# house-sensor4pre.net
KiCad netlist of a schematic drawn in EAGLE
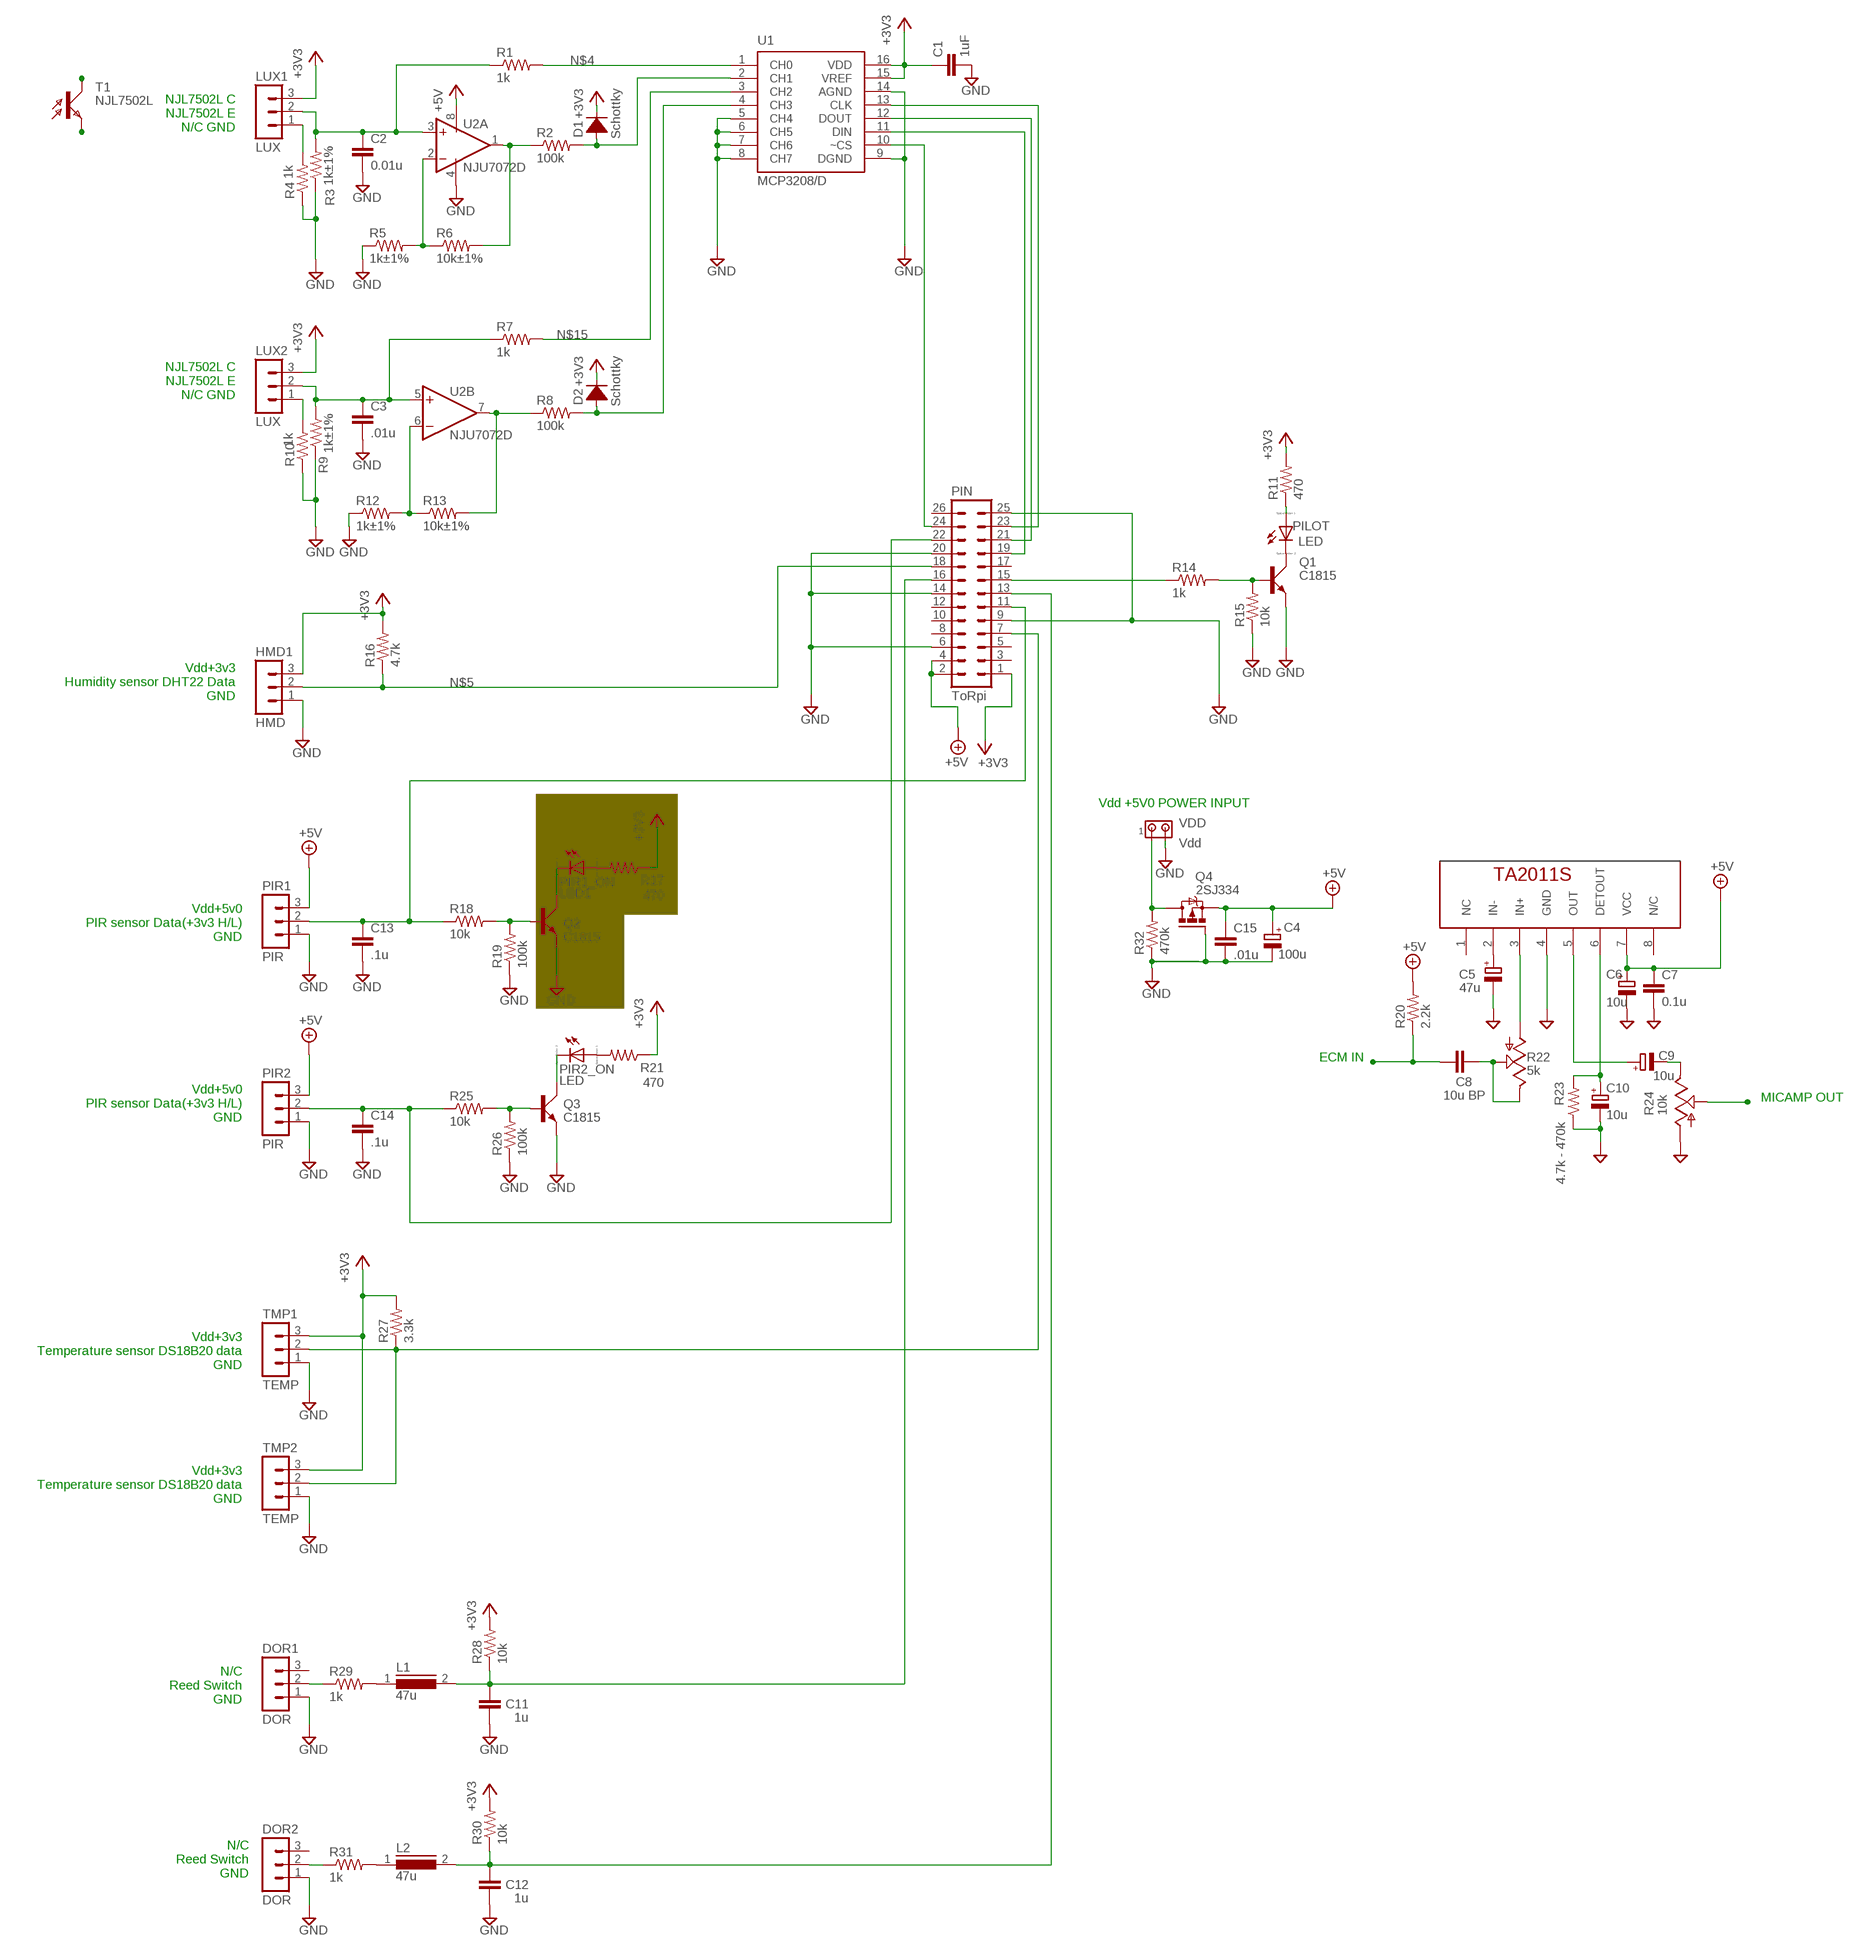
[diagram p0: schematic, sheet 1]

(export (version "E")
  (design (tool "Eeschema 10.0.6"))
  (components
    (comp (ref "C1")
      (value "1uF")
      (footprint "eagle-import:C025-025X050")
      (libsource (lib "eagle-import") (part "C-EU025-025X050"))
    )
    (comp (ref "C2")
      (value "0.01u")
      (footprint "eagle-import:C025-024X044")
      (libsource (lib "eagle-import") (part "C-EU025-024X044"))
    )
    (comp (ref "C3")
      (value ".01u")
      (footprint "eagle-import:C025-024X044")
      (libsource (lib "eagle-import") (part "C-EU025-024X044"))
    )
    (comp (ref "C4")
      (value "100u")
      (footprint "eagle-import:E1,8-4")
      (libsource (lib "eagle-import") (part "resistor_CPOL-EUE1.8-4"))
    )
    (comp (ref "C5")
      (value "47u")
      (footprint "eagle-import:E1,8-4")
      (libsource (lib "eagle-import") (part "rcl_CPOL-EUE1.8-4"))
    )
    (comp (ref "C6")
      (value "10u")
      (footprint "eagle-import:E1,8-4")
      (libsource (lib "eagle-import") (part "rcl_CPOL-EUE1.8-4"))
    )
    (comp (ref "C7")
      (value "0.1u")
      (footprint "eagle-import:C025-024X044")
      (libsource (lib "eagle-import") (part "C"))
    )
    (comp (ref "C8")
      (value "10u BP")
      (footprint "eagle-import:C025-024X044")
      (libsource (lib "eagle-import") (part "C"))
    )
    (comp (ref "C9")
      (value "10u")
      (footprint "eagle-import:E1,8-4")
      (libsource (lib "eagle-import") (part "rcl_CPOL-EUE1.8-4"))
    )
    (comp (ref "C10")
      (value "10u")
      (footprint "eagle-import:E1,8-4")
      (libsource (lib "eagle-import") (part "CPOL-EUE1.8-4"))
    )
    (comp (ref "C11")
      (value "1u")
      (footprint "eagle-import:C050-024X044")
      (libsource (lib "eagle-import") (part "C-EU050-024X044"))
    )
    (comp (ref "C12")
      (value "1u")
      (footprint "eagle-import:C050-024X044")
      (libsource (lib "eagle-import") (part "C-EU050-024X044"))
    )
    (comp (ref "C13")
      (value ".1u")
      (footprint "eagle-import:C025-030X050")
      (libsource (lib "eagle-import") (part "C-EU025-030X050"))
    )
    (comp (ref "C14")
      (value ".1u")
      (footprint "eagle-import:C025-030X050")
      (libsource (lib "eagle-import") (part "C-EU025-030X050"))
    )
    (comp (ref "C15")
      (value ".01u")
      (footprint "eagle-import:C025-025X050")
      (libsource (lib "eagle-import") (part "C-EU025-025X050"))
    )
    (comp (ref "D1")
      (value "Schottky")
      (footprint "eagle-import:DIODE_V")
      (libsource (lib "eagle-import") (part "DIODE_V"))
    )
    (comp (ref "D2")
      (value "Schottky")
      (footprint "eagle-import:DIODE_V")
      (libsource (lib "eagle-import") (part "DIODE_V"))
    )
    (comp (ref "DOR1")
      (value "DOR")
      (footprint "eagle-import:MA03-1")
      (libsource (lib "eagle-import") (part "MA03-1"))
    )
    (comp (ref "DOR2")
      (value "DOR")
      (footprint "eagle-import:MA03-1")
      (libsource (lib "eagle-import") (part "MA03-1"))
    )
    (comp (ref "HMD1")
      (value "HMD")
      (footprint "eagle-import:MA03-1")
      (libsource (lib "eagle-import") (part "MA03-1"))
    )
    (comp (ref "L1")
      (value "47u")
      (footprint "eagle-import:LBC-SE")
      (libsource (lib "eagle-import") (part "LBC-SE"))
    )
    (comp (ref "L2")
      (value "47u")
      (footprint "eagle-import:LBC-SE")
      (libsource (lib "eagle-import") (part "LBC-SE"))
    )
    (comp (ref "LUX1")
      (value "LUX")
      (footprint "eagle-import:MA03-1")
      (libsource (lib "eagle-import") (part "MA03-1"))
    )
    (comp (ref "LUX2")
      (value "LUX")
      (footprint "eagle-import:MA03-1")
      (libsource (lib "eagle-import") (part "MA03-1"))
    )
    (comp (ref "PILOT")
      (value "LED")
      (footprint "eagle-import:LED_LD260")
      (libsource (lib "eagle-import") (part "LED_ELD260"))
    )
    (comp (ref "PIN")
      (value "ToRpi")
      (footprint "eagle-import:MA13-2")
      (libsource (lib "eagle-import") (part "MA13-2"))
    )
    (comp (ref "PIR1")
      (value "PIR")
      (footprint "eagle-import:MA03-1")
      (libsource (lib "eagle-import") (part "MA03-1"))
    )
    (comp (ref "PIR1_ON")
      (value "LED1")
      (footprint "eagle-import:LED_LD260")
      (libsource (lib "eagle-import") (part "LED_ELD260"))
    )
    (comp (ref "PIR2")
      (value "PIR")
      (footprint "eagle-import:MA03-1")
      (libsource (lib "eagle-import") (part "MA03-1"))
    )
    (comp (ref "PIR2_ON")
      (value "LED")
      (footprint "eagle-import:LED_LD260")
      (libsource (lib "eagle-import") (part "LED_ELD260"))
    )
    (comp (ref "Q1")
      (value "C1815")
      (footprint "eagle-import:TO92-LINE")
      (libsource (lib "eagle-import") (part "2SC1815"))
    )
    (comp (ref "Q2")
      (value "C1815")
      (footprint "eagle-import:TO92-LINE")
      (libsource (lib "eagle-import") (part "2SC1815"))
    )
    (comp (ref "Q3")
      (value "C1815")
      (footprint "eagle-import:TO92-LINE")
      (libsource (lib "eagle-import") (part "2SC1815"))
    )
    (comp (ref "R1")
      (value "1k")
      (footprint "eagle-import:0207_2V")
      (libsource (lib "eagle-import") (part "R-US_0207/2V"))
    )
    (comp (ref "R2")
      (value "100k")
      (footprint "eagle-import:0207_10")
      (libsource (lib "eagle-import") (part "R-US_0207/10"))
    )
    (comp (ref "R3")
      (value "1k±1%")
      (footprint "eagle-import:0207_2V")
      (libsource (lib "eagle-import") (part "R-US_0207/2V"))
    )
    (comp (ref "R4")
      (value "1k")
      (footprint "eagle-import:0309V")
      (libsource (lib "eagle-import") (part "R-US_0309/V"))
    )
    (comp (ref "R5")
      (value "1k±1%")
      (footprint "eagle-import:0207_2V")
      (libsource (lib "eagle-import") (part "R-US_0207/2V"))
    )
    (comp (ref "R6")
      (value "10k±1%")
      (footprint "eagle-import:0207_2V")
      (libsource (lib "eagle-import") (part "R-US_0207/2V"))
    )
    (comp (ref "R7")
      (value "1k")
      (footprint "eagle-import:0207_2V")
      (libsource (lib "eagle-import") (part "R-US_0207/2V"))
    )
    (comp (ref "R8")
      (value "100k")
      (footprint "eagle-import:0204_7")
      (libsource (lib "eagle-import") (part "R-US_0204/7"))
    )
    (comp (ref "R9")
      (value "1k±1%")
      (footprint "eagle-import:0207_2V")
      (libsource (lib "eagle-import") (part "R-US_0207/2V"))
    )
    (comp (ref "R10")
      (value "1k")
      (footprint "eagle-import:0309V")
      (libsource (lib "eagle-import") (part "R-US_0309/V"))
    )
    (comp (ref "R11")
      (value "470")
      (footprint "eagle-import:0207_2V")
      (libsource (lib "eagle-import") (part "R-US_0207/2V"))
    )
    (comp (ref "R12")
      (value "1k±1%")
      (footprint "eagle-import:0207_2V")
      (libsource (lib "eagle-import") (part "R-US_0207/2V"))
    )
    (comp (ref "R13")
      (value "10k±1%")
      (footprint "eagle-import:0207_2V")
      (libsource (lib "eagle-import") (part "R-US_0207/2V"))
    )
    (comp (ref "R14")
      (value "1k")
      (footprint "eagle-import:0204V")
      (libsource (lib "eagle-import") (part "R-US_0204/2V"))
    )
    (comp (ref "R15")
      (value "10k")
      (footprint "eagle-import:0207_2V")
      (libsource (lib "eagle-import") (part "R-US_0207/2V"))
    )
    (comp (ref "R16")
      (value "4.7k")
      (footprint "eagle-import:0207_2V")
      (libsource (lib "eagle-import") (part "R-US_0207/2V"))
    )
    (comp (ref "R17")
      (value "470")
      (footprint "eagle-import:0204V")
      (libsource (lib "eagle-import") (part "R-US_0204/2V"))
    )
    (comp (ref "R18")
      (value "10k")
      (footprint "eagle-import:0204V")
      (libsource (lib "eagle-import") (part "R-US_0204/2V"))
    )
    (comp (ref "R19")
      (value "100k")
      (footprint "eagle-import:0204V")
      (libsource (lib "eagle-import") (part "R-US_0204/2V"))
    )
    (comp (ref "R20")
      (value "2.2k")
      (footprint "eagle-import:0207_2V")
      (libsource (lib "eagle-import") (part "R-US_0207/2V"))
    )
    (comp (ref "R21")
      (value "470")
      (footprint "eagle-import:0204V")
      (libsource (lib "eagle-import") (part "R-US_0204/2V"))
    )
    (comp (ref "R22")
      (value "5k")
      (footprint "eagle-import:B25P")
      (libsource (lib "eagle-import") (part "TRIM_US-B25P"))
    )
    (comp (ref "R23")
      (value "4.7k - 470k")
      (footprint "eagle-import:0207_2V")
      (libsource (lib "eagle-import") (part "R-US_0207/2V"))
    )
    (comp (ref "R24")
      (value "10k")
      (footprint "eagle-import:B25P")
      (libsource (lib "eagle-import") (part "TRIM_US-B25P"))
    )
    (comp (ref "R25")
      (value "10k")
      (footprint "eagle-import:0204V")
      (libsource (lib "eagle-import") (part "R-US_0204/2V"))
    )
    (comp (ref "R26")
      (value "100k")
      (footprint "eagle-import:0204V")
      (libsource (lib "eagle-import") (part "R-US_0204/2V"))
    )
    (comp (ref "R27")
      (value "3.3k")
      (footprint "eagle-import:0204V")
      (libsource (lib "eagle-import") (part "R-US_0204/2V"))
    )
    (comp (ref "R28")
      (value "10k")
      (footprint "eagle-import:0204V")
      (libsource (lib "eagle-import") (part "R-US_0204/2V"))
    )
    (comp (ref "R29")
      (value "1k")
      (footprint "eagle-import:0207_5V")
      (libsource (lib "eagle-import") (part "R-US_0207/5V"))
    )
    (comp (ref "R30")
      (value "10k")
      (footprint "eagle-import:0204V")
      (libsource (lib "eagle-import") (part "R-US_0204/2V"))
    )
    (comp (ref "R31")
      (value "1k")
      (footprint "eagle-import:0207_5V")
      (libsource (lib "eagle-import") (part "R-US_0207/5V"))
    )
    (comp (ref "R32")
      (value "470k")
      (footprint "eagle-import:0204V")
      (libsource (lib "eagle-import") (part "R-US_0204/2V"))
    )
    (comp (ref "T1")
      (value "NJL7502L")
      (footprint "eagle-import:BPX81")
      (libsource (lib "eagle-import") (part "BPX81"))
    )
    (comp (ref "TMP1")
      (value "TEMP")
      (footprint "eagle-import:MA03-1")
      (libsource (lib "eagle-import") (part "MA03-1"))
    )
    (comp (ref "TMP2")
      (value "TEMP")
      (footprint "eagle-import:MA03-1")
      (libsource (lib "eagle-import") (part "MA03-1"))
    )
    (comp (ref "U$1")
      (value "TA2011S")
      (footprint "eagle-import:SIP8")
      (libsource (lib "eagle-import") (part "TA2011S"))
    )
    (comp (ref "U1")
      (value "MCP3208/D")
      (footprint "eagle-import:DIL16")
      (libsource (lib "eagle-import") (part "MCP3208/DIP"))
    )
    (comp (ref "U2")
      (value "NJU7072D")
      (footprint "eagle-import:DIL08")
      (libsource (lib "eagle-import") (part "LM358N"))
    )
    (comp (ref "VDD")
      (value "Vdd")
      (footprint "eagle-import:10X02MTA")
      (libsource (lib "eagle-import") (part "MTA02-100"))
    )
  )
  (nets
    (net (code "1") (name "+3V3") (class "Default")
      (node (ref "C1") (pin "1") (pinfunction "1_1") (pintype "passive"))
      (node (ref "D1") (pin "P$2") (pinfunction "K_P$2") (pintype "passive"))
      (node (ref "D2") (pin "P$2") (pinfunction "K_P$2") (pintype "passive"))
      (node (ref "HMD1") (pin "3") (pinfunction "3_3") (pintype "passive"))
      (node (ref "LUX1") (pin "3") (pinfunction "3_3") (pintype "passive"))
      (node (ref "LUX2") (pin "3") (pinfunction "3_3") (pintype "passive"))
      (node (ref "PIN") (pin "1") (pinfunction "1_1") (pintype "passive"))
      (node (ref "R11") (pin "2") (pinfunction "2_2") (pintype "passive"))
      (node (ref "R16") (pin "2") (pinfunction "2_2") (pintype "passive"))
      (node (ref "R17") (pin "1") (pinfunction "1_1") (pintype "passive"))
      (node (ref "R21") (pin "1") (pinfunction "1_1") (pintype "passive"))
      (node (ref "R27") (pin "2") (pinfunction "2_2") (pintype "passive"))
      (node (ref "R28") (pin "2") (pinfunction "2_2") (pintype "passive"))
      (node (ref "R30") (pin "2") (pinfunction "2_2") (pintype "passive"))
      (node (ref "TMP1") (pin "3") (pinfunction "3_3") (pintype "passive"))
      (node (ref "TMP2") (pin "3") (pinfunction "3_3") (pintype "passive"))
      (node (ref "U1") (pin "15") (pinfunction "VREF_15") (pintype "bidirectional"))
      (node (ref "U1") (pin "16") (pinfunction "VDD_16") (pintype "bidirectional"))
    )
    (net (code "2") (name "+5V") (class "Default")
      (node (ref "C15") (pin "1") (pinfunction "1_1") (pintype "passive"))
      (node (ref "C4") (pin "+") (pinfunction "+_+") (pintype "passive"))
      (node (ref "C6") (pin "+") (pinfunction "+_+") (pintype "passive"))
      (node (ref "C7") (pin "1") (pinfunction "1_1") (pintype "passive"))
      (node (ref "PIN") (pin "2") (pinfunction "2_2") (pintype "passive"))
      (node (ref "PIN") (pin "4") (pinfunction "4_4") (pintype "passive"))
      (node (ref "PIR1") (pin "3") (pinfunction "3_3") (pintype "passive"))
      (node (ref "PIR2") (pin "3") (pinfunction "3_3") (pintype "passive"))
      (node (ref "R20") (pin "2") (pinfunction "2_2") (pintype "passive"))
      (node (ref "U$1") (pin "7") (pinfunction "VCC_7") (pintype "power_in"))
      (node (ref "U2") (pin "8") (pinfunction "V+_8") (pintype "power_in"))
    )
    (net (code "3") (name "/N$4") (class "Default")
      (node (ref "R1") (pin "2") (pinfunction "2_2") (pintype "passive"))
      (node (ref "U1") (pin "1") (pinfunction "CH0_1") (pintype "bidirectional"))
    )
    (net (code "4") (name "/N$5") (class "Default")
      (node (ref "HMD1") (pin "2") (pinfunction "2_2") (pintype "passive"))
      (node (ref "PIN") (pin "18") (pinfunction "18_18") (pintype "passive"))
      (node (ref "R16") (pin "1") (pinfunction "1_1") (pintype "passive"))
    )
    (net (code "5") (name "/N$15") (class "Default")
      (node (ref "R7") (pin "2") (pinfunction "2_2") (pintype "passive"))
      (node (ref "U1") (pin "3") (pinfunction "CH2_3") (pintype "bidirectional"))
    )
    (net (code "6") (name "GND") (class "Default")
      (node (ref "C1") (pin "2") (pinfunction "2_2") (pintype "passive"))
      (node (ref "C10") (pin "-") (pinfunction "-_-") (pintype "passive"))
      (node (ref "C11") (pin "1") (pinfunction "1_1") (pintype "passive"))
      (node (ref "C12") (pin "1") (pinfunction "1_1") (pintype "passive"))
      (node (ref "C13") (pin "2") (pinfunction "2_2") (pintype "passive"))
      (node (ref "C14") (pin "2") (pinfunction "2_2") (pintype "passive"))
      (node (ref "C15") (pin "2") (pinfunction "2_2") (pintype "passive"))
      (node (ref "C2") (pin "2") (pinfunction "2_2") (pintype "passive"))
      (node (ref "C3") (pin "2") (pinfunction "2_2") (pintype "passive"))
      (node (ref "C4") (pin "-") (pinfunction "-_-") (pintype "passive"))
      (node (ref "C5") (pin "-") (pinfunction "-_-") (pintype "passive"))
      (node (ref "C6") (pin "-") (pinfunction "-_-") (pintype "passive"))
      (node (ref "C7") (pin "2") (pinfunction "2_2") (pintype "passive"))
      (node (ref "DOR1") (pin "1") (pinfunction "1_1") (pintype "passive"))
      (node (ref "DOR2") (pin "1") (pinfunction "1_1") (pintype "passive"))
      (node (ref "HMD1") (pin "1") (pinfunction "1_1") (pintype "passive"))
      (node (ref "PIN") (pin "14") (pinfunction "14_14") (pintype "passive"))
      (node (ref "PIN") (pin "20") (pinfunction "20_20") (pintype "passive"))
      (node (ref "PIN") (pin "25") (pinfunction "25_25") (pintype "passive"))
      (node (ref "PIN") (pin "6") (pinfunction "6_6") (pintype "passive"))
      (node (ref "PIN") (pin "9") (pinfunction "9_9") (pintype "passive"))
      (node (ref "PIR1") (pin "1") (pinfunction "1_1") (pintype "passive"))
      (node (ref "PIR2") (pin "1") (pinfunction "1_1") (pintype "passive"))
      (node (ref "Q1") (pin "3") (pinfunction "E_3") (pintype "passive"))
      (node (ref "Q2") (pin "3") (pinfunction "E_3") (pintype "passive"))
      (node (ref "Q3") (pin "3") (pinfunction "E_3") (pintype "passive"))
      (node (ref "R10") (pin "1") (pinfunction "1_1") (pintype "passive"))
      (node (ref "R12") (pin "1") (pinfunction "1_1") (pintype "passive"))
      (node (ref "R15") (pin "1") (pinfunction "1_1") (pintype "passive"))
      (node (ref "R19") (pin "1") (pinfunction "1_1") (pintype "passive"))
      (node (ref "R23") (pin "1") (pinfunction "1_1") (pintype "passive"))
      (node (ref "R24") (pin "A") (pinfunction "A_A") (pintype "passive"))
      (node (ref "R26") (pin "1") (pinfunction "1_1") (pintype "passive"))
      (node (ref "R3") (pin "1") (pinfunction "1_1") (pintype "passive"))
      (node (ref "R32") (pin "1") (pinfunction "1_1") (pintype "passive"))
      (node (ref "R4") (pin "1") (pinfunction "1_1") (pintype "passive"))
      (node (ref "R5") (pin "1") (pinfunction "1_1") (pintype "passive"))
      (node (ref "R9") (pin "1") (pinfunction "1_1") (pintype "passive"))
      (node (ref "TMP1") (pin "1") (pinfunction "1_1") (pintype "passive"))
      (node (ref "TMP2") (pin "1") (pinfunction "1_1") (pintype "passive"))
      (node (ref "U$1") (pin "4") (pinfunction "GND_4") (pintype "power_in"))
      (node (ref "U1") (pin "14") (pinfunction "AGND_14") (pintype "bidirectional"))
      (node (ref "U1") (pin "5") (pinfunction "CH4_5") (pintype "bidirectional"))
      (node (ref "U1") (pin "6") (pinfunction "CH5_6") (pintype "bidirectional"))
      (node (ref "U1") (pin "7") (pinfunction "CH6_7") (pintype "bidirectional"))
      (node (ref "U1") (pin "8") (pinfunction "CH7_8") (pintype "bidirectional"))
      (node (ref "U1") (pin "9") (pinfunction "DGND_9") (pintype "bidirectional"))
      (node (ref "U2") (pin "4") (pinfunction "V-_4") (pintype "power_in"))
      (node (ref "VDD") (pin "2") (pinfunction "2_2") (pintype "passive"))
    )
    (net (code "7") (name "Net-(C8-Pad1)") (class "Default")
      (node (ref "C8") (pin "1") (pinfunction "1_1") (pintype "passive"))
      (node (ref "R20") (pin "1") (pinfunction "1_1") (pintype "passive"))
    )
    (net (code "8") (name "Net-(C8-Pad2)") (class "Default")
      (node (ref "C8") (pin "2") (pinfunction "2_2") (pintype "passive"))
      (node (ref "R22") (pin "E") (pinfunction "E_E") (pintype "passive"))
      (node (ref "R22") (pin "S") (pinfunction "S_S") (pintype "passive"))
    )
    (net (code "9") (name "Net-(C9-Pad-)") (class "Default")
      (node (ref "C9") (pin "-") (pinfunction "-_-") (pintype "passive"))
      (node (ref "R24") (pin "E") (pinfunction "E_E") (pintype "passive"))
    )
    (net (code "10") (name "Net-(C11-Pad2)") (class "Default")
      (node (ref "C11") (pin "2") (pinfunction "2_2") (pintype "passive"))
      (node (ref "L1") (pin "2") (pinfunction "2_2") (pintype "passive"))
      (node (ref "PIN") (pin "16") (pinfunction "16_16") (pintype "passive"))
      (node (ref "R28") (pin "1") (pinfunction "1_1") (pintype "passive"))
    )
    (net (code "11") (name "Net-(C12-Pad2)") (class "Default")
      (node (ref "C12") (pin "2") (pinfunction "2_2") (pintype "passive"))
      (node (ref "L2") (pin "2") (pinfunction "2_2") (pintype "passive"))
      (node (ref "PIN") (pin "13") (pinfunction "13_13") (pintype "passive"))
      (node (ref "R30") (pin "1") (pinfunction "1_1") (pintype "passive"))
    )
    (net (code "12") (name "Net-(C13-Pad1)") (class "Default")
      (node (ref "C13") (pin "1") (pinfunction "1_1") (pintype "passive"))
      (node (ref "PIN") (pin "11") (pinfunction "11_11") (pintype "passive"))
      (node (ref "PIR1") (pin "2") (pinfunction "2_2") (pintype "passive"))
      (node (ref "R18") (pin "1") (pinfunction "1_1") (pintype "passive"))
    )
    (net (code "13") (name "Net-(C14-Pad1)") (class "Default")
      (node (ref "C14") (pin "1") (pinfunction "1_1") (pintype "passive"))
      (node (ref "PIN") (pin "22") (pinfunction "22_22") (pintype "passive"))
      (node (ref "PIR2") (pin "2") (pinfunction "2_2") (pintype "passive"))
      (node (ref "R25") (pin "1") (pinfunction "1_1") (pintype "passive"))
    )
    (net (code "14") (name "Net-(D1-A)") (class "Default")
      (node (ref "D1") (pin "P$1") (pinfunction "A_P$1") (pintype "passive"))
      (node (ref "R2") (pin "2") (pinfunction "2_2") (pintype "passive"))
      (node (ref "U1") (pin "2") (pinfunction "CH1_2") (pintype "bidirectional"))
    )
    (net (code "15") (name "Net-(D2-A)") (class "Default")
      (node (ref "D2") (pin "P$1") (pinfunction "A_P$1") (pintype "passive"))
      (node (ref "R8") (pin "2") (pinfunction "2_2") (pintype "passive"))
      (node (ref "U1") (pin "4") (pinfunction "CH3_4") (pintype "bidirectional"))
    )
    (net (code "16") (name "Net-(DOR1-Pad2)") (class "Default")
      (node (ref "DOR1") (pin "2") (pinfunction "2_2") (pintype "passive"))
      (node (ref "R29") (pin "1") (pinfunction "1_1") (pintype "passive"))
    )
    (net (code "17") (name "Net-(DOR2-Pad2)") (class "Default")
      (node (ref "DOR2") (pin "2") (pinfunction "2_2") (pintype "passive"))
      (node (ref "R31") (pin "1") (pinfunction "1_1") (pintype "passive"))
    )
    (net (code "18") (name "Net-(L1-Pad1)") (class "Default")
      (node (ref "L1") (pin "1") (pinfunction "1_1") (pintype "passive"))
      (node (ref "R29") (pin "2") (pinfunction "2_2") (pintype "passive"))
    )
    (net (code "19") (name "Net-(L2-Pad1)") (class "Default")
      (node (ref "L2") (pin "1") (pinfunction "1_1") (pintype "passive"))
      (node (ref "R31") (pin "2") (pinfunction "2_2") (pintype "passive"))
    )
    (net (code "20") (name "Net-(LUX1-Pad1)") (class "Default")
      (node (ref "LUX1") (pin "1") (pinfunction "1_1") (pintype "passive"))
      (node (ref "R4") (pin "2") (pinfunction "2_2") (pintype "passive"))
    )
    (net (code "21") (name "Net-(LUX2-Pad1)") (class "Default")
      (node (ref "LUX2") (pin "1") (pinfunction "1_1") (pintype "passive"))
      (node (ref "R10") (pin "2") (pinfunction "2_2") (pintype "passive"))
    )
    (net (code "22") (name "Net-(PILOT-C)") (class "Default")
      (node (ref "PILOT") (pin "K") (pinfunction "C_K") (pintype "passive"))
      (node (ref "Q1") (pin "2") (pinfunction "C_2") (pintype "passive"))
    )
    (net (code "23") (name "Net-(PILOT-PadA)") (class "Default")
      (node (ref "PILOT") (pin "A") (pinfunction "A_A") (pintype "passive"))
      (node (ref "R11") (pin "1") (pinfunction "1_1") (pintype "passive"))
    )
    (net (code "24") (name "Net-(PIN-Pad7)") (class "Default")
      (node (ref "PIN") (pin "7") (pinfunction "7_7") (pintype "passive"))
      (node (ref "R27") (pin "1") (pinfunction "1_1") (pintype "passive"))
      (node (ref "TMP1") (pin "2") (pinfunction "2_2") (pintype "passive"))
      (node (ref "TMP2") (pin "2") (pinfunction "2_2") (pintype "passive"))
    )
    (net (code "25") (name "Net-(PIN-Pad15)") (class "Default")
      (node (ref "PIN") (pin "15") (pinfunction "15_15") (pintype "passive"))
      (node (ref "R14") (pin "1") (pinfunction "1_1") (pintype "passive"))
    )
    (net (code "26") (name "Net-(PIR1_ON-C)") (class "Default")
      (node (ref "PIR1_ON") (pin "K") (pinfunction "C_K") (pintype "passive"))
      (node (ref "Q2") (pin "2") (pinfunction "C_2") (pintype "passive"))
    )
    (net (code "27") (name "Net-(PIR1_ON-PadA)") (class "Default")
      (node (ref "PIR1_ON") (pin "A") (pinfunction "A_A") (pintype "passive"))
      (node (ref "R17") (pin "2") (pinfunction "2_2") (pintype "passive"))
    )
    (net (code "28") (name "Net-(PIR2_ON-C)") (class "Default")
      (node (ref "PIR2_ON") (pin "K") (pinfunction "C_K") (pintype "passive"))
      (node (ref "Q3") (pin "2") (pinfunction "C_2") (pintype "passive"))
    )
    (net (code "29") (name "Net-(PIR2_ON-PadA)") (class "Default")
      (node (ref "PIR2_ON") (pin "A") (pinfunction "A_A") (pintype "passive"))
      (node (ref "R21") (pin "2") (pinfunction "2_2") (pintype "passive"))
    )
    (net (code "30") (name "Net-(Q1-B)") (class "Default")
      (node (ref "Q1") (pin "1") (pinfunction "B_1") (pintype "passive"))
      (node (ref "R14") (pin "2") (pinfunction "2_2") (pintype "passive"))
      (node (ref "R15") (pin "2") (pinfunction "2_2") (pintype "passive"))
    )
    (net (code "31") (name "Net-(Q2-B)") (class "Default")
      (node (ref "Q2") (pin "1") (pinfunction "B_1") (pintype "passive"))
      (node (ref "R18") (pin "2") (pinfunction "2_2") (pintype "passive"))
      (node (ref "R19") (pin "2") (pinfunction "2_2") (pintype "passive"))
    )
    (net (code "32") (name "Net-(Q3-B)") (class "Default")
      (node (ref "Q3") (pin "1") (pinfunction "B_1") (pintype "passive"))
      (node (ref "R25") (pin "2") (pinfunction "2_2") (pintype "passive"))
      (node (ref "R26") (pin "2") (pinfunction "2_2") (pintype "passive"))
    )
    (net (code "33") (name "Net-(R32-Pad2)") (class "Default")
      (node (ref "R32") (pin "2") (pinfunction "2_2") (pintype "passive"))
      (node (ref "VDD") (pin "1") (pinfunction "1_1") (pintype "passive"))
    )
    (net (code "34") (name "Net-(U$1-DETOUT)") (class "Default")
      (node (ref "C10") (pin "+") (pinfunction "+_+") (pintype "passive"))
      (node (ref "R23") (pin "2") (pinfunction "2_2") (pintype "passive"))
      (node (ref "U$1") (pin "6") (pinfunction "DETOUT_6") (pintype "input"))
    )
    (net (code "35") (name "Net-(U$1-IN+)") (class "Default")
      (node (ref "R22") (pin "A") (pinfunction "A_A") (pintype "passive"))
      (node (ref "U$1") (pin "3") (pinfunction "IN+_3") (pintype "input"))
    )
    (net (code "36") (name "Net-(U$1-IN-)") (class "Default")
      (node (ref "C5") (pin "+") (pinfunction "+_+") (pintype "passive"))
      (node (ref "U$1") (pin "2") (pinfunction "IN-_2") (pintype "input"))
    )
    (net (code "37") (name "Net-(U$1-OUT)") (class "Default")
      (node (ref "C9") (pin "+") (pinfunction "+_+") (pintype "passive"))
      (node (ref "U$1") (pin "5") (pinfunction "OUT_5") (pintype "output"))
    )
    (net (code "38") (name "Net-(U1-CLK)") (class "Default")
      (node (ref "PIN") (pin "23") (pinfunction "23_23") (pintype "passive"))
      (node (ref "U1") (pin "13") (pinfunction "CLK_13") (pintype "bidirectional"))
    )
    (net (code "39") (name "Net-(U1-DIN)") (class "Default")
      (node (ref "PIN") (pin "19") (pinfunction "19_19") (pintype "passive"))
      (node (ref "U1") (pin "11") (pinfunction "DIN_11") (pintype "bidirectional"))
    )
    (net (code "40") (name "Net-(U1-DOUT)") (class "Default")
      (node (ref "PIN") (pin "21") (pinfunction "21_21") (pintype "passive"))
      (node (ref "U1") (pin "12") (pinfunction "DOUT_12") (pintype "bidirectional"))
    )
    (net (code "41") (name "Net-(U1-~{CS})") (class "Default")
      (node (ref "PIN") (pin "24") (pinfunction "24_24") (pintype "passive"))
      (node (ref "U1") (pin "10") (pinfunction "~{CS}_10") (pintype "bidirectional"))
    )
    (net (code "42") (name "Net-(U2A-+IN)") (class "Default")
      (node (ref "C2") (pin "1") (pinfunction "1_1") (pintype "passive"))
      (node (ref "LUX1") (pin "2") (pinfunction "2_2") (pintype "passive"))
      (node (ref "R1") (pin "1") (pinfunction "1_1") (pintype "passive"))
      (node (ref "R3") (pin "2") (pinfunction "2_2") (pintype "passive"))
      (node (ref "U2") (pin "3") (pinfunction "+IN_3") (pintype "input"))
    )
    (net (code "43") (name "Net-(U2A--IN)") (class "Default")
      (node (ref "R5") (pin "2") (pinfunction "2_2") (pintype "passive"))
      (node (ref "R6") (pin "1") (pinfunction "1_1") (pintype "passive"))
      (node (ref "U2") (pin "2") (pinfunction "-IN_2") (pintype "input"))
    )
    (net (code "44") (name "Net-(U2A-OUT)") (class "Default")
      (node (ref "R2") (pin "1") (pinfunction "1_1") (pintype "passive"))
      (node (ref "R6") (pin "2") (pinfunction "2_2") (pintype "passive"))
      (node (ref "U2") (pin "1") (pinfunction "OUT_1") (pintype "output"))
    )
    (net (code "45") (name "Net-(U2B-+IN)") (class "Default")
      (node (ref "C3") (pin "1") (pinfunction "1_1") (pintype "passive"))
      (node (ref "LUX2") (pin "2") (pinfunction "2_2") (pintype "passive"))
      (node (ref "R7") (pin "1") (pinfunction "1_1") (pintype "passive"))
      (node (ref "R9") (pin "2") (pinfunction "2_2") (pintype "passive"))
      (node (ref "U2") (pin "5") (pinfunction "+IN_5") (pintype "input"))
    )
    (net (code "46") (name "Net-(U2B--IN)") (class "Default")
      (node (ref "R12") (pin "2") (pinfunction "2_2") (pintype "passive"))
      (node (ref "R13") (pin "1") (pinfunction "1_1") (pintype "passive"))
      (node (ref "U2") (pin "6") (pinfunction "-IN_6") (pintype "input"))
    )
    (net (code "47") (name "Net-(U2B-OUT)") (class "Default")
      (node (ref "R13") (pin "2") (pinfunction "2_2") (pintype "passive"))
      (node (ref "R8") (pin "1") (pinfunction "1_1") (pintype "passive"))
      (node (ref "U2") (pin "7") (pinfunction "OUT_7") (pintype "output"))
    )
    (net (code "48") (name "unconnected-(DOR1-Pad3)") (class "Default")
      (node (ref "DOR1") (pin "3") (pinfunction "3_3") (pintype "passive"))
    )
    (net (code "49") (name "unconnected-(DOR2-Pad3)") (class "Default")
      (node (ref "DOR2") (pin "3") (pinfunction "3_3") (pintype "passive"))
    )
    (net (code "50") (name "unconnected-(PIN-Pad3)") (class "Default")
      (node (ref "PIN") (pin "3") (pinfunction "3_3") (pintype "passive"))
    )
    (net (code "51") (name "unconnected-(PIN-Pad5)") (class "Default")
      (node (ref "PIN") (pin "5") (pinfunction "5_5") (pintype "passive"))
    )
    (net (code "52") (name "unconnected-(PIN-Pad8)") (class "Default")
      (node (ref "PIN") (pin "8") (pinfunction "8_8") (pintype "passive"))
    )
    (net (code "53") (name "unconnected-(PIN-Pad10)") (class "Default")
      (node (ref "PIN") (pin "10") (pinfunction "10_10") (pintype "passive"))
    )
    (net (code "54") (name "unconnected-(PIN-Pad12)") (class "Default")
      (node (ref "PIN") (pin "12") (pinfunction "12_12") (pintype "passive"))
    )
    (net (code "55") (name "unconnected-(PIN-Pad17)") (class "Default")
      (node (ref "PIN") (pin "17") (pinfunction "17_17") (pintype "passive"))
    )
    (net (code "56") (name "unconnected-(PIN-Pad26)") (class "Default")
      (node (ref "PIN") (pin "26") (pinfunction "26_26") (pintype "passive"))
    )
    (net (code "57") (name "unconnected-(R24-PadS)") (class "Default")
      (node (ref "R24") (pin "S") (pinfunction "S_S") (pintype "passive"))
    )
    (net (code "58") (name "unconnected-(T1-PadC)") (class "Default")
      (node (ref "T1") (pin "C") (pinfunction "C_C") (pintype "passive"))
    )
    (net (code "59") (name "unconnected-(T1-PadE)") (class "Default")
      (node (ref "T1") (pin "E") (pinfunction "E_E") (pintype "passive"))
    )
    (net (code "60") (name "unconnected-(U$1-NC-Pad1)") (class "Default")
      (node (ref "U$1") (pin "1") (pinfunction "NC_1") (pintype "no_connect"))
    )
    (net (code "61") (name "unconnected-(U$1-N{slash}C-Pad8)") (class "Default")
      (node (ref "U$1") (pin "8") (pinfunction "N/C_8") (pintype "no_connect"))
    )
  )
)
